# ThermoE.net
KiCad netlist of a schematic drawn in Altium Designer
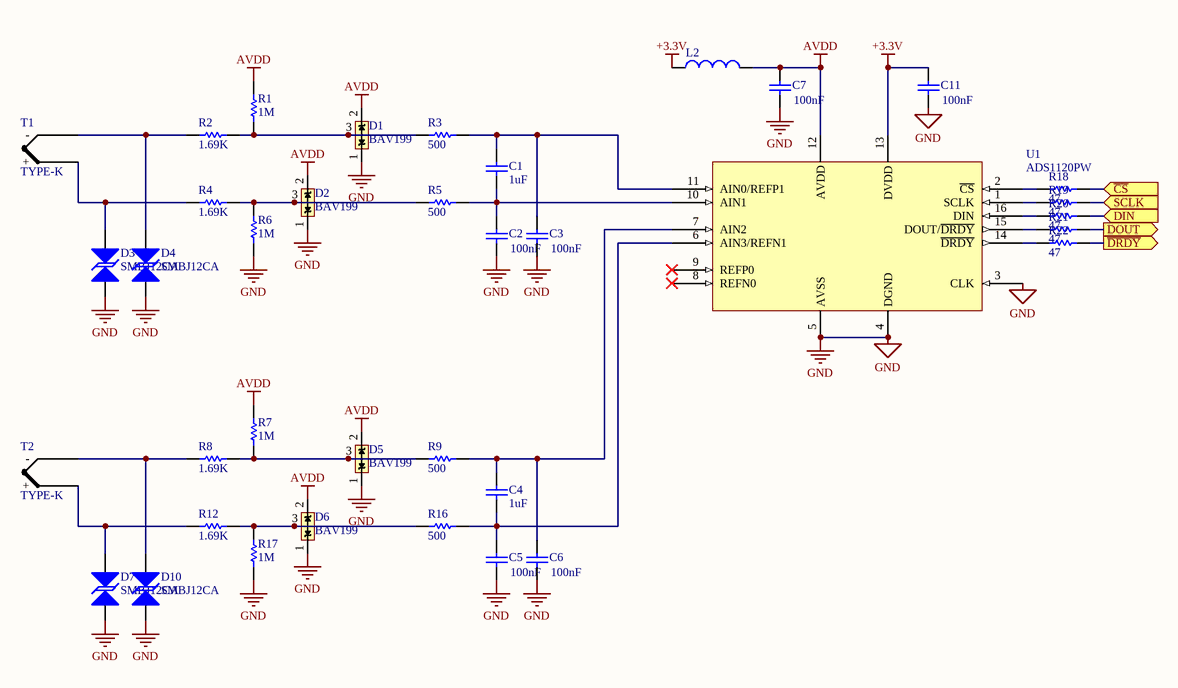
[diagram p0: ThermoE.SchDoc]

(export (version "E")
  (design (tool "Eeschema 10.0.6"))
  (components
    (comp (ref "C1")
      (value "1uF")
      (footprint "c603")
      (description "Capacitor")
      (fields (field (name "DESIGNER") "Parsa Malekpour"))
      (libsource (lib "ParsaLibrary") (part "Cap"))
    )
    (comp (ref "C2")
      (value "100nF")
      (footprint "c603")
      (description "Capacitor")
      (fields (field (name "DESIGNER") "Parsa Malekpour"))
      (libsource (lib "ParsaLibrary") (part "Cap"))
    )
    (comp (ref "C3")
      (value "100nF")
      (footprint "c603")
      (description "Capacitor")
      (fields (field (name "DESIGNER") "Parsa Malekpour"))
      (libsource (lib "ParsaLibrary") (part "Cap"))
    )
    (comp (ref "C4")
      (value "1uF")
      (footprint "c603")
      (description "Capacitor")
      (fields (field (name "DESIGNER") "Parsa Malekpour"))
      (libsource (lib "ParsaLibrary") (part "Cap"))
    )
    (comp (ref "C5")
      (value "100nF")
      (footprint "c603")
      (description "Capacitor")
      (fields (field (name "DESIGNER") "Parsa Malekpour"))
      (libsource (lib "ParsaLibrary") (part "Cap"))
    )
    (comp (ref "C6")
      (value "100nF")
      (footprint "c603")
      (description "Capacitor")
      (fields (field (name "DESIGNER") "Parsa Malekpour"))
      (libsource (lib "ParsaLibrary") (part "Cap"))
    )
    (comp (ref "C7")
      (value "100nF")
      (footprint "C603")
      (description "Capacitor")
      (fields (field (name "DESIGNER") "Parsa Malekpour"))
      (libsource (lib "ParsaLibrary") (part "Cap"))
    )
    (comp (ref "C11")
      (value "100nF")
      (footprint "C603")
      (description "Capacitor")
      (fields (field (name "DESIGNER") "Parsa Malekpour"))
      (libsource (lib "ParsaLibrary") (part "Cap"))
    )
    (comp (ref "D1") (value "BAV199") (footprint "SOT-23") (libsource (lib "ParsaLibrary") (part "BAV199")))
    (comp (ref "D2") (value "BAV199") (footprint "SOT-23") (libsource (lib "ParsaLibrary") (part "BAV199")))
    (comp (ref "D3")
      (value "SMBJ12CA")
      (footprint "DO-214AA")
      (description "Surface Mount Transient Voltage Suppressors Diode")
      (libsource (lib "ParsaLibrary") (part "SMBJxxCA"))
    )
    (comp (ref "D4")
      (value "SMBJ12CA")
      (footprint "DO-214AA")
      (description "Surface Mount Transient Voltage Suppressors Diode")
      (libsource (lib "ParsaLibrary") (part "SMBJxxCA"))
    )
    (comp (ref "D5") (value "BAV199") (footprint "SOT-23") (libsource (lib "ParsaLibrary") (part "BAV199")))
    (comp (ref "D6") (value "BAV199") (footprint "SOT-23") (libsource (lib "ParsaLibrary") (part "BAV199")))
    (comp (ref "D7")
      (value "SMBJ12CA")
      (footprint "DO-214AA")
      (description "Surface Mount Transient Voltage Suppressors Diode")
      (libsource (lib "ParsaLibrary") (part "SMBJxxCA"))
    )
    (comp (ref "D10")
      (value "SMBJ12CA")
      (footprint "DO-214AA")
      (description "Surface Mount Transient Voltage Suppressors Diode")
      (libsource (lib "ParsaLibrary") (part "SMBJxxCA"))
    )
    (comp (ref "L2")
      (value "1K")
      (footprint "r805")
      (description "FERRITE BEAD")
      (fields (field (name "PUBLISHER") "Altium Limited"))
      (libsource (lib "ParsaLibrary") (part "Ferrite Bead"))
    )
    (comp (ref "R1")
      (value "1M")
      (footprint "R0603")
      (description "Resistor")
      (fields (field (name "DESIGNER") "Parsa Malekpour"))
      (libsource (lib "ParsaLibrary") (part "Resistor"))
    )
    (comp (ref "R2")
      (value "1.69K")
      (footprint "R0603")
      (description "Resistor")
      (fields (field (name "DESIGNER") "Parsa Malekpour"))
      (libsource (lib "ParsaLibrary") (part "Resistor"))
    )
    (comp (ref "R3")
      (value "500")
      (footprint "R0603")
      (description "Resistor")
      (fields (field (name "DESIGNER") "Parsa Malekpour"))
      (libsource (lib "ParsaLibrary") (part "Resistor"))
    )
    (comp (ref "R4")
      (value "1.69K")
      (footprint "R0603")
      (description "Resistor")
      (fields (field (name "DESIGNER") "Parsa Malekpour"))
      (libsource (lib "ParsaLibrary") (part "Resistor"))
    )
    (comp (ref "R5")
      (value "500")
      (footprint "R0603")
      (description "Resistor")
      (fields (field (name "DESIGNER") "Parsa Malekpour"))
      (libsource (lib "ParsaLibrary") (part "Resistor"))
    )
    (comp (ref "R6")
      (value "1M")
      (footprint "R0603")
      (description "Resistor")
      (fields (field (name "DESIGNER") "Parsa Malekpour"))
      (libsource (lib "ParsaLibrary") (part "Resistor"))
    )
    (comp (ref "R7")
      (value "1M")
      (footprint "R0603")
      (description "Resistor")
      (fields (field (name "DESIGNER") "Parsa Malekpour"))
      (libsource (lib "ParsaLibrary") (part "Resistor"))
    )
    (comp (ref "R8")
      (value "1.69K")
      (footprint "R0603")
      (description "Resistor")
      (fields (field (name "DESIGNER") "Parsa Malekpour"))
      (libsource (lib "ParsaLibrary") (part "Resistor"))
    )
    (comp (ref "R9")
      (value "500")
      (footprint "R0603")
      (description "Resistor")
      (fields (field (name "DESIGNER") "Parsa Malekpour"))
      (libsource (lib "ParsaLibrary") (part "Resistor"))
    )
    (comp (ref "R12")
      (value "1.69K")
      (footprint "R0603")
      (description "Resistor")
      (fields (field (name "DESIGNER") "Parsa Malekpour"))
      (libsource (lib "ParsaLibrary") (part "Resistor"))
    )
    (comp (ref "R16")
      (value "500")
      (footprint "R0603")
      (description "Resistor")
      (fields (field (name "DESIGNER") "Parsa Malekpour"))
      (libsource (lib "ParsaLibrary") (part "Resistor"))
    )
    (comp (ref "R17")
      (value "1M")
      (footprint "R0603")
      (description "Resistor")
      (fields (field (name "DESIGNER") "Parsa Malekpour"))
      (libsource (lib "ParsaLibrary") (part "Resistor"))
    )
    (comp (ref "R18")
      (value "47")
      (footprint "R0603")
      (description "Resistor")
      (fields (field (name "DESIGNER") "Parsa Malekpour"))
      (libsource (lib "ParsaLibrary") (part "Resistor"))
    )
    (comp (ref "R19")
      (value "47")
      (footprint "R0603")
      (description "Resistor")
      (fields (field (name "DESIGNER") "Parsa Malekpour"))
      (libsource (lib "ParsaLibrary") (part "Resistor"))
    )
    (comp (ref "R20")
      (value "47")
      (footprint "R0603")
      (description "Resistor")
      (fields (field (name "DESIGNER") "Parsa Malekpour"))
      (libsource (lib "ParsaLibrary") (part "Resistor"))
    )
    (comp (ref "R21")
      (value "47")
      (footprint "R0603")
      (description "Resistor")
      (fields (field (name "DESIGNER") "Parsa Malekpour"))
      (libsource (lib "ParsaLibrary") (part "Resistor"))
    )
    (comp (ref "R22")
      (value "47")
      (footprint "R0603")
      (description "Resistor")
      (fields (field (name "DESIGNER") "Parsa Malekpour"))
      (libsource (lib "ParsaLibrary") (part "Resistor"))
    )
    (comp (ref "T1")
      (value "TYPE-K")
      (footprint "PCC-SMP")
      (libsource (lib "ParsaLibrary") (part "THERMOCOUPLE"))
    )
    (comp (ref "T2")
      (value "TYPE-K")
      (footprint "PCC-SMP")
      (libsource (lib "ParsaLibrary") (part "THERMOCOUPLE"))
    )
    (comp (ref "U1")
      (value "ADS1120PW")
      (footprint "TSSOP-16")
      (description "ADS1120 4-Channel, 2-kSPS, Low-Power, 16-Bit ADC with Integrated PGA and Reference")
      (libsource (lib "ParsaLibrary") (part "ADS1120PW"))
    )
  )
  (nets
    (net (code "1") (name "+3.3V") (class "Default")
      (node (ref "C11") (pin "2") (pinfunction "2_2") (pintype "passive"))
      (node (ref "L2") (pin "1") (pinfunction "1_1") (pintype "passive"))
      (node (ref "U1") (pin "13") (pinfunction "DVDD_13") (pintype "power_in"))
    )
    (net (code "2") (name "/DIN") (class "Default")
      (node (ref "R20") (pin "1") (pinfunction "1_1") (pintype "passive"))
    )
    (net (code "3") (name "/DOUT") (class "Default")
      (node (ref "R21") (pin "1") (pinfunction "1_1") (pintype "passive"))
    )
    (net (code "4") (name "/SCLK") (class "Default")
      (node (ref "R19") (pin "1") (pinfunction "1_1") (pintype "passive"))
    )
    (net (code "5") (name "/~{CS}") (class "Default")
      (node (ref "R18") (pin "1") (pinfunction "1_1") (pintype "passive"))
    )
    (net (code "6") (name "/~{DRDY}") (class "Default")
      (node (ref "R22") (pin "1") (pinfunction "1_1") (pintype "passive"))
    )
    (net (code "7") (name "AVDD") (class "Default")
      (node (ref "C7") (pin "2") (pinfunction "2_2") (pintype "passive"))
      (node (ref "D1") (pin "2") (pinfunction "K2_2") (pintype "passive"))
      (node (ref "D2") (pin "2") (pinfunction "K2_2") (pintype "passive"))
      (node (ref "D5") (pin "2") (pinfunction "K2_2") (pintype "passive"))
      (node (ref "D6") (pin "2") (pinfunction "K2_2") (pintype "passive"))
      (node (ref "L2") (pin "2") (pinfunction "2_2") (pintype "passive"))
      (node (ref "R1") (pin "2") (pinfunction "2_2") (pintype "passive"))
      (node (ref "R7") (pin "2") (pinfunction "2_2") (pintype "passive"))
      (node (ref "U1") (pin "12") (pinfunction "AVDD_12") (pintype "power_in"))
    )
    (net (code "8") (name "GND") (class "Default")
      (node (ref "C11") (pin "1") (pinfunction "1_1") (pintype "passive"))
      (node (ref "C2") (pin "1") (pinfunction "1_1") (pintype "passive"))
      (node (ref "C3") (pin "1") (pinfunction "1_1") (pintype "passive"))
      (node (ref "C5") (pin "1") (pinfunction "1_1") (pintype "passive"))
      (node (ref "C6") (pin "1") (pinfunction "1_1") (pintype "passive"))
      (node (ref "C7") (pin "1") (pinfunction "1_1") (pintype "passive"))
      (node (ref "D1") (pin "1") (pinfunction "A1_1") (pintype "passive"))
      (node (ref "D10") (pin "1") (pinfunction "A_1") (pintype "passive"))
      (node (ref "D2") (pin "1") (pinfunction "A1_1") (pintype "passive"))
      (node (ref "D3") (pin "1") (pinfunction "A_1") (pintype "passive"))
      (node (ref "D4") (pin "1") (pinfunction "A_1") (pintype "passive"))
      (node (ref "D5") (pin "1") (pinfunction "A1_1") (pintype "passive"))
      (node (ref "D6") (pin "1") (pinfunction "A1_1") (pintype "passive"))
      (node (ref "D7") (pin "1") (pinfunction "A_1") (pintype "passive"))
      (node (ref "R17") (pin "1") (pinfunction "1_1") (pintype "passive"))
      (node (ref "R6") (pin "1") (pinfunction "1_1") (pintype "passive"))
      (node (ref "U1") (pin "3") (pinfunction "CLK_3") (pintype "input"))
      (node (ref "U1") (pin "4") (pinfunction "DGND_4") (pintype "power_in"))
      (node (ref "U1") (pin "5") (pinfunction "AVSS_5") (pintype "power_in"))
    )
    (net (code "9") (name "Net-(D1-C)") (class "Default")
      (node (ref "D1") (pin "3") (pinfunction "C_3") (pintype "passive"))
      (node (ref "R1") (pin "1") (pinfunction "1_1") (pintype "passive"))
      (node (ref "R2") (pin "1") (pinfunction "1_1") (pintype "passive"))
      (node (ref "R3") (pin "2") (pinfunction "2_2") (pintype "passive"))
    )
    (net (code "10") (name "Net-(D2-C)") (class "Default")
      (node (ref "D2") (pin "3") (pinfunction "C_3") (pintype "passive"))
      (node (ref "R4") (pin "1") (pinfunction "1_1") (pintype "passive"))
      (node (ref "R5") (pin "2") (pinfunction "2_2") (pintype "passive"))
      (node (ref "R6") (pin "2") (pinfunction "2_2") (pintype "passive"))
    )
    (net (code "11") (name "Net-(D3-K)") (class "Default")
      (node (ref "D3") (pin "2") (pinfunction "K_2") (pintype "passive"))
      (node (ref "R4") (pin "2") (pinfunction "2_2") (pintype "passive"))
      (node (ref "T1") (pin "2") (pinfunction "+_2") (pintype "passive"))
    )
    (net (code "12") (name "Net-(D4-K)") (class "Default")
      (node (ref "D4") (pin "2") (pinfunction "K_2") (pintype "passive"))
      (node (ref "R2") (pin "2") (pinfunction "2_2") (pintype "passive"))
      (node (ref "T1") (pin "1") (pinfunction "-_1") (pintype "passive"))
    )
    (net (code "13") (name "Net-(D5-C)") (class "Default")
      (node (ref "D5") (pin "3") (pinfunction "C_3") (pintype "passive"))
      (node (ref "R7") (pin "1") (pinfunction "1_1") (pintype "passive"))
      (node (ref "R8") (pin "1") (pinfunction "1_1") (pintype "passive"))
      (node (ref "R9") (pin "2") (pinfunction "2_2") (pintype "passive"))
    )
    (net (code "14") (name "Net-(D6-C)") (class "Default")
      (node (ref "D6") (pin "3") (pinfunction "C_3") (pintype "passive"))
      (node (ref "R12") (pin "1") (pinfunction "1_1") (pintype "passive"))
      (node (ref "R16") (pin "2") (pinfunction "2_2") (pintype "passive"))
      (node (ref "R17") (pin "2") (pinfunction "2_2") (pintype "passive"))
    )
    (net (code "15") (name "Net-(D7-K)") (class "Default")
      (node (ref "D7") (pin "2") (pinfunction "K_2") (pintype "passive"))
      (node (ref "R12") (pin "2") (pinfunction "2_2") (pintype "passive"))
      (node (ref "T2") (pin "2") (pinfunction "+_2") (pintype "passive"))
    )
    (net (code "16") (name "Net-(D10-K)") (class "Default")
      (node (ref "D10") (pin "2") (pinfunction "K_2") (pintype "passive"))
      (node (ref "R8") (pin "2") (pinfunction "2_2") (pintype "passive"))
      (node (ref "T2") (pin "1") (pinfunction "-_1") (pintype "passive"))
    )
    (net (code "17") (name "Net-(U1-AIN0{slash}REFP1)") (class "Default")
      (node (ref "C1") (pin "2") (pinfunction "2_2") (pintype "passive"))
      (node (ref "C3") (pin "2") (pinfunction "2_2") (pintype "passive"))
      (node (ref "R3") (pin "1") (pinfunction "1_1") (pintype "passive"))
      (node (ref "U1") (pin "11") (pinfunction "AIN0/REFP1_11") (pintype "input"))
    )
    (net (code "18") (name "Net-(U1-AIN1)") (class "Default")
      (node (ref "C1") (pin "1") (pinfunction "1_1") (pintype "passive"))
      (node (ref "C2") (pin "2") (pinfunction "2_2") (pintype "passive"))
      (node (ref "R5") (pin "1") (pinfunction "1_1") (pintype "passive"))
      (node (ref "U1") (pin "10") (pinfunction "AIN1_10") (pintype "input"))
    )
    (net (code "19") (name "Net-(U1-AIN2)") (class "Default")
      (node (ref "C4") (pin "2") (pinfunction "2_2") (pintype "passive"))
      (node (ref "C6") (pin "2") (pinfunction "2_2") (pintype "passive"))
      (node (ref "R9") (pin "1") (pinfunction "1_1") (pintype "passive"))
      (node (ref "U1") (pin "7") (pinfunction "AIN2_7") (pintype "input"))
    )
    (net (code "20") (name "Net-(U1-AIN3{slash}REFN1)") (class "Default")
      (node (ref "C4") (pin "1") (pinfunction "1_1") (pintype "passive"))
      (node (ref "C5") (pin "2") (pinfunction "2_2") (pintype "passive"))
      (node (ref "R16") (pin "1") (pinfunction "1_1") (pintype "passive"))
      (node (ref "U1") (pin "6") (pinfunction "AIN3/REFN1_6") (pintype "input"))
    )
    (net (code "21") (name "Net-(U1-DIN)") (class "Default")
      (node (ref "R20") (pin "2") (pinfunction "2_2") (pintype "passive"))
      (node (ref "U1") (pin "16") (pinfunction "DIN_16") (pintype "input"))
    )
    (net (code "22") (name "Net-(U1-DOUT{slash}~{DRDY})") (class "Default")
      (node (ref "R21") (pin "2") (pinfunction "2_2") (pintype "passive"))
      (node (ref "U1") (pin "15") (pinfunction "DOUT/~{DRDY}_15") (pintype "output"))
    )
    (net (code "23") (name "Net-(U1-SCLK)") (class "Default")
      (node (ref "R19") (pin "2") (pinfunction "2_2") (pintype "passive"))
      (node (ref "U1") (pin "1") (pinfunction "SCLK_1") (pintype "input"))
    )
    (net (code "24") (name "Net-(U1-~{CS})") (class "Default")
      (node (ref "R18") (pin "2") (pinfunction "2_2") (pintype "passive"))
      (node (ref "U1") (pin "2") (pinfunction "~{CS}_2") (pintype "input"))
    )
    (net (code "25") (name "Net-(U1-~{DRDY})") (class "Default")
      (node (ref "R22") (pin "2") (pinfunction "2_2") (pintype "passive"))
      (node (ref "U1") (pin "14") (pinfunction "~{DRDY}_14") (pintype "output"))
    )
    (net (code "26") (name "unconnected-(U1-REFN0-Pad8)") (class "Default")
      (node (ref "U1") (pin "8") (pinfunction "REFN0_8") (pintype "input+no_connect"))
    )
    (net (code "27") (name "unconnected-(U1-REFP0-Pad9)") (class "Default")
      (node (ref "U1") (pin "9") (pinfunction "REFP0_9") (pintype "input+no_connect"))
    )
  )
)
